# MIDI_TESTER.net
KiCad netlist of a schematic drawn in EAGLE
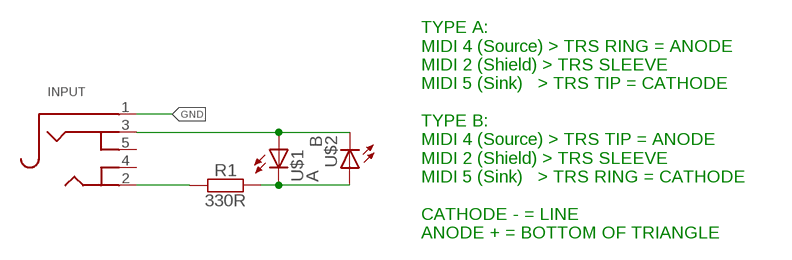
[diagram p0: schematic, sheet 1]

(export (version "E")
  (design (tool "Eeschema 10.0.6"))
  (components
    (comp (ref "INPUT")
      (value "AUDIO_3.5MMJACK")
      (footprint "eagle-import:4UCONN_19269")
      (libsource (lib "eagle-import") (part "AUDIO_3.5MMJACK"))
    )
    (comp (ref "R1")
      (value "330R")
      (footprint "eagle-import:C0603")
      (libsource (lib "eagle-import") (part "RESISTOR-0603"))
    )
    (comp (ref "U$1")
      (value "A")
      (footprint "eagle-import:LED-1206-REVERSE-PLATED")
      (libsource (lib "eagle-import") (part "LED-1206-REVERSE_PLATEPLATED"))
    )
    (comp (ref "U$2")
      (value "B")
      (footprint "eagle-import:LED-1206-REVERSE-PLATED")
      (libsource (lib "eagle-import") (part "LED-1206-REVERSE_PLATEPLATED"))
    )
  )
  (nets
    (net (code "1") (name "GND") (class "Default")
      (node (ref "INPUT") (pin "1") (pinfunction "P$1_1") (pintype "bidirectional"))
    )
    (net (code "2") (name "Net-(INPUT-P$2)") (class "Default")
      (node (ref "INPUT") (pin "3") (pinfunction "P$2_3") (pintype "bidirectional"))
      (node (ref "U$1") (pin "A") (pinfunction "A_A") (pintype "passive"))
      (node (ref "U$2") (pin "C") (pinfunction "C_C") (pintype "passive"))
    )
    (net (code "3") (name "Net-(INPUT-P$5)") (class "Default")
      (node (ref "INPUT") (pin "2") (pinfunction "P$5_2") (pintype "bidirectional"))
      (node (ref "R1") (pin "1") (pinfunction "1_1") (pintype "passive"))
    )
    (net (code "4") (name "Net-(R1-Pad2)") (class "Default")
      (node (ref "R1") (pin "2") (pinfunction "2_2") (pintype "passive"))
      (node (ref "U$1") (pin "C") (pinfunction "C_C") (pintype "passive"))
      (node (ref "U$2") (pin "A") (pinfunction "A_A") (pintype "passive"))
    )
    (net (code "5") (name "unconnected-(INPUT-P$3-Pad5)") (class "Default")
      (node (ref "INPUT") (pin "5") (pinfunction "P$3_5") (pintype "bidirectional"))
    )
    (net (code "6") (name "unconnected-(INPUT-P$4-Pad4)") (class "Default")
      (node (ref "INPUT") (pin "4") (pinfunction "P$4_4") (pintype "bidirectional"))
    )
    (net (code "7") (name "unconnected-(U$1-P$1-PadHOLE_BOTTOM)") (class "Default")
      (node (ref "U$1") (pin "HOLE_BOTTOM") (pinfunction "P$1_HOLE_BOTTOM") (pintype "no_connect"))
    )
    (net (code "8") (name "unconnected-(U$1-P$1-PadHOLE_TOP)") (class "Default")
      (node (ref "U$1") (pin "HOLE_TOP") (pinfunction "P$1_HOLE_TOP") (pintype "no_connect"))
    )
    (net (code "9") (name "unconnected-(U$2-P$1-PadHOLE_BOTTOM)") (class "Default")
      (node (ref "U$2") (pin "HOLE_BOTTOM") (pinfunction "P$1_HOLE_BOTTOM") (pintype "no_connect"))
    )
    (net (code "10") (name "unconnected-(U$2-P$1-PadHOLE_TOP)") (class "Default")
      (node (ref "U$2") (pin "HOLE_TOP") (pinfunction "P$1_HOLE_TOP") (pintype "no_connect"))
    )
  )
)
